# SCH_MiniPrintV1_2025-03-26.net
KiCad netlist of a schematic drawn in EasyEDA
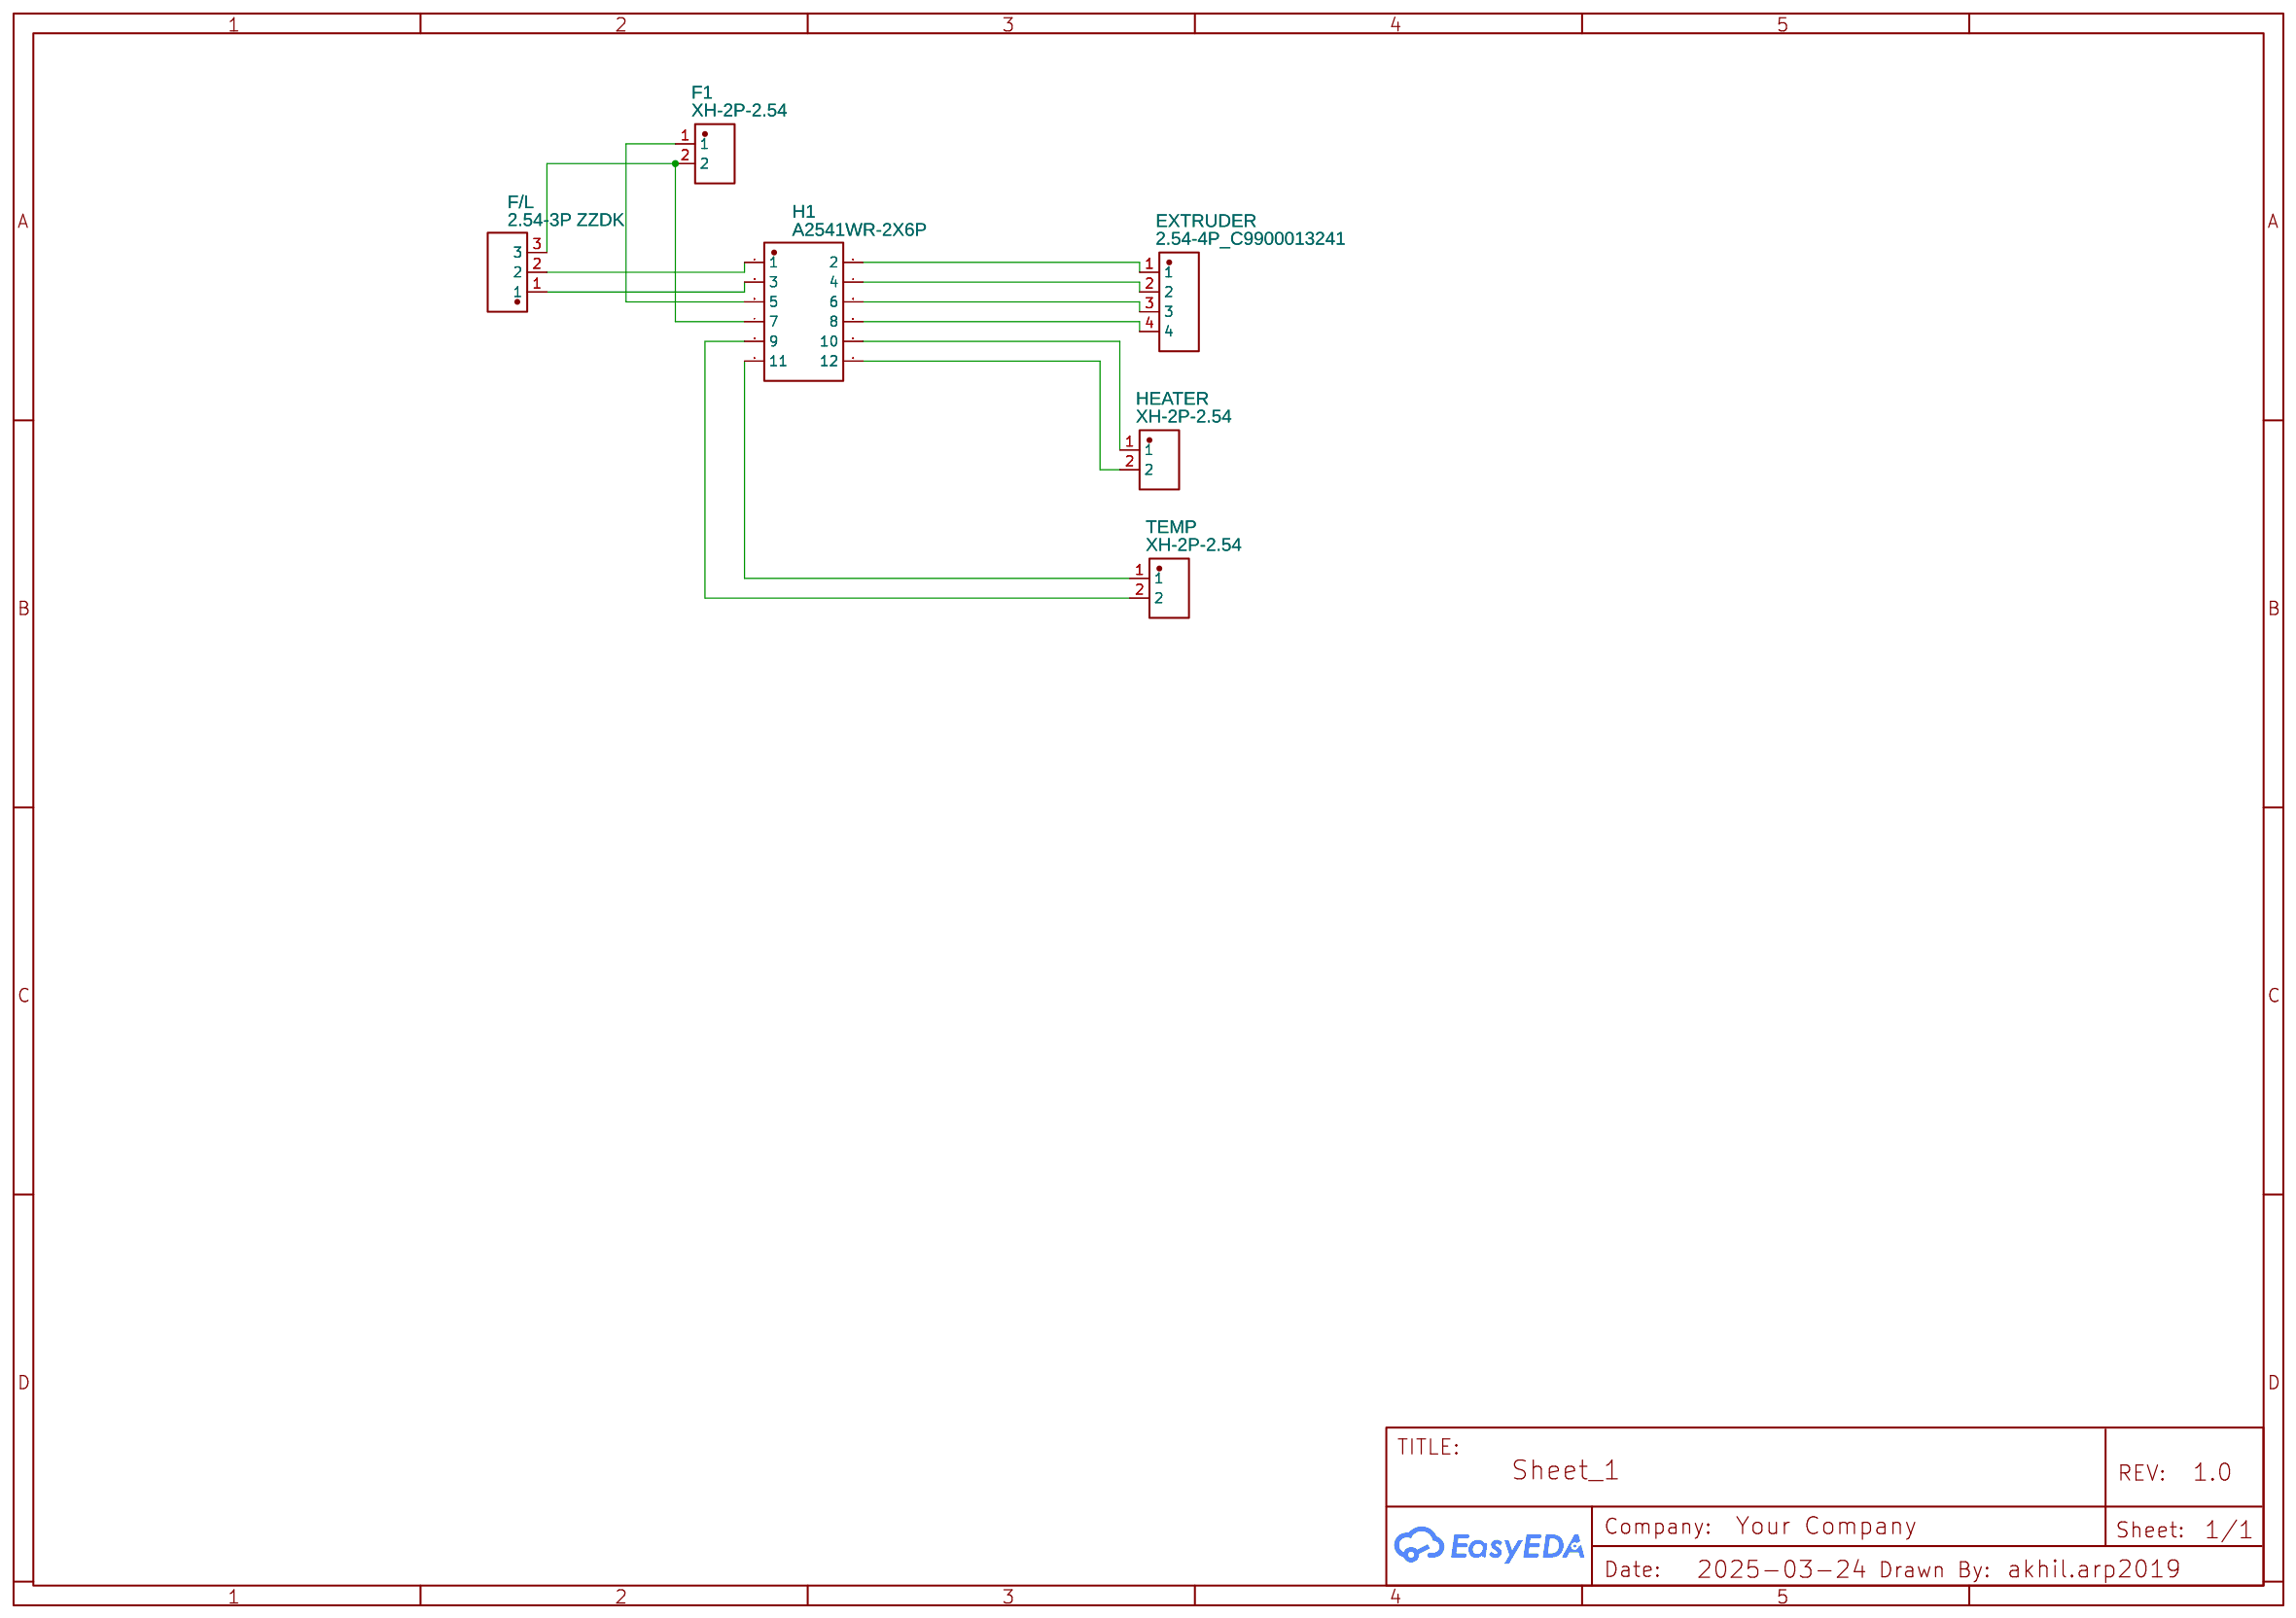
[diagram p0: schematic sheet]

(export (version "E")
  (design (tool "Eeschema 10.0.6"))
  (components
    (comp (ref "EXTRUDER")
      (value "2.54-4P_C9900013241")
      (fields (field (name "Manufacturer Part") "2.54-4P"))
      (libsource (lib "") (part "2.54-4P_C9900013241"))
    )
    (comp (ref "F/L")
      (value "2.54-3P ZZDK")
      (fields (field (name "Manufacturer") "SHOU HAN(首韩)"))
      (libsource (lib "") (part "2.54-3P ZZDK"))
    )
    (comp (ref "F1") (value "XH-2P-2.54") (libsource (lib "") (part "XH-2P-2.54_1")))
    (comp (ref "H1")
      (value "A2541WR-2X6P")
      (fields (field (name "Manufacturer Part") "A2541WR-2x6P") (field (name "Manufacturer") "CJT(长江连接器)"))
      (libsource (lib "") (part "A2541WR-2X6P"))
    )
    (comp (ref "HEATER") (value "XH-2P-2.54") (libsource (lib "") (part "XH-2P-2.54_2")))
    (comp (ref "TEMP") (value "XH-2P-2.54") (libsource (lib "") (part "XH-2P-2.54")))
  )
  (nets
    (net (code "1") (name "Net-(EXTRUDER-Pad1)") (class "Default")
      (node (ref "EXTRUDER") (pin "1") (pinfunction "1_1") (pintype "unspecified"))
      (node (ref "H1") (pin "2") (pinfunction "2_2") (pintype "unspecified"))
    )
    (net (code "2") (name "Net-(EXTRUDER-Pad2)") (class "Default")
      (node (ref "EXTRUDER") (pin "2") (pinfunction "2_2") (pintype "unspecified"))
      (node (ref "H1") (pin "4") (pinfunction "4_4") (pintype "unspecified"))
    )
    (net (code "3") (name "Net-(EXTRUDER-Pad3)") (class "Default")
      (node (ref "EXTRUDER") (pin "3") (pinfunction "3_3") (pintype "unspecified"))
      (node (ref "H1") (pin "6") (pinfunction "6_6") (pintype "unspecified"))
    )
    (net (code "4") (name "Net-(EXTRUDER-Pad4)") (class "Default")
      (node (ref "EXTRUDER") (pin "4") (pinfunction "4_4") (pintype "unspecified"))
      (node (ref "H1") (pin "8") (pinfunction "8_8") (pintype "unspecified"))
    )
    (net (code "5") (name "Net-(F/L-Pad1)") (class "Default")
      (node (ref "F/L") (pin "1") (pinfunction "1_1") (pintype "unspecified"))
      (node (ref "H1") (pin "3") (pinfunction "3_3") (pintype "unspecified"))
    )
    (net (code "6") (name "Net-(F/L-Pad2)") (class "Default")
      (node (ref "F/L") (pin "2") (pinfunction "2_2") (pintype "unspecified"))
      (node (ref "H1") (pin "1") (pinfunction "1_1") (pintype "unspecified"))
    )
    (net (code "7") (name "Net-(F/L-Pad3)") (class "Default")
      (node (ref "F/L") (pin "3") (pinfunction "3_3") (pintype "unspecified"))
      (node (ref "F1") (pin "2") (pinfunction "2_2") (pintype "unspecified"))
      (node (ref "H1") (pin "7") (pinfunction "7_7") (pintype "unspecified"))
    )
    (net (code "8") (name "Net-(F1-Pad1)") (class "Default")
      (node (ref "F1") (pin "1") (pinfunction "1_1") (pintype "unspecified"))
      (node (ref "H1") (pin "5") (pinfunction "5_5") (pintype "unspecified"))
    )
    (net (code "9") (name "Net-(H1-Pad9)") (class "Default")
      (node (ref "H1") (pin "9") (pinfunction "9_9") (pintype "unspecified"))
      (node (ref "TEMP") (pin "2") (pinfunction "2_2") (pintype "unspecified"))
    )
    (net (code "10") (name "Net-(H1-Pad10)") (class "Default")
      (node (ref "H1") (pin "10") (pinfunction "10_10") (pintype "unspecified"))
      (node (ref "HEATER") (pin "1") (pinfunction "1_1") (pintype "unspecified"))
    )
    (net (code "11") (name "Net-(H1-Pad11)") (class "Default")
      (node (ref "H1") (pin "11") (pinfunction "11_11") (pintype "unspecified"))
      (node (ref "TEMP") (pin "1") (pinfunction "1_1") (pintype "unspecified"))
    )
    (net (code "12") (name "Net-(H1-Pad12)") (class "Default")
      (node (ref "H1") (pin "12") (pinfunction "12_12") (pintype "unspecified"))
      (node (ref "HEATER") (pin "2") (pinfunction "2_2") (pintype "unspecified"))
    )
  )
)
